# lpc11c14.net
KiCad netlist of a schematic drawn in Altium Designer
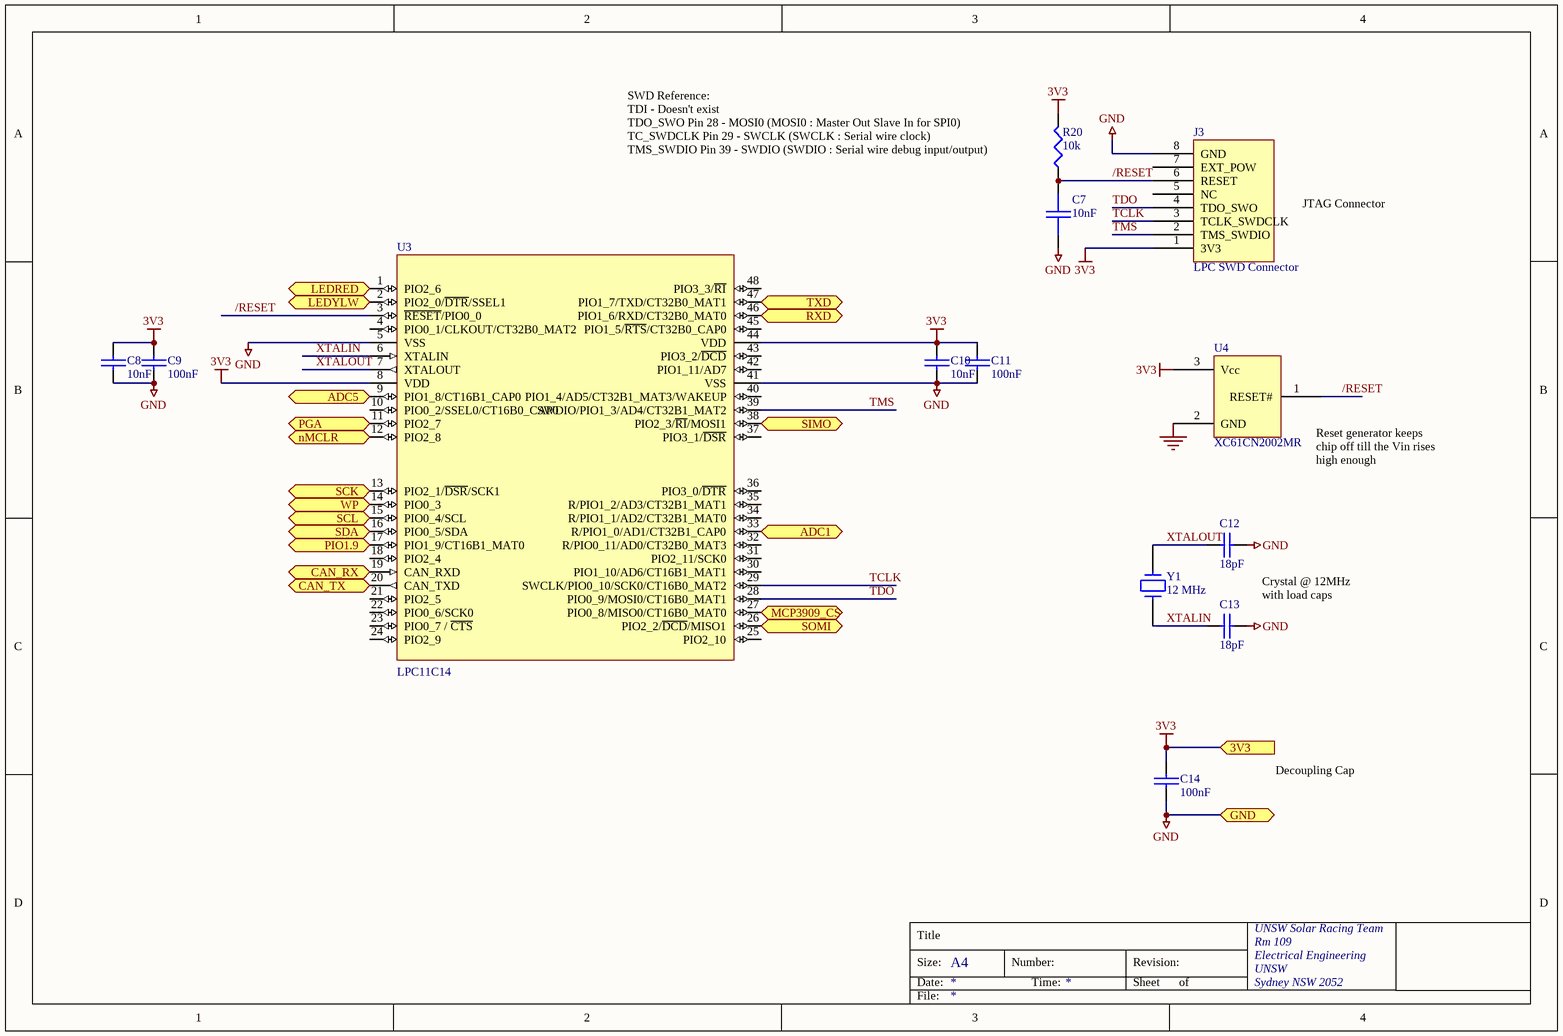
[diagram p0: lpc11c14.SchDoc]

(export (version "E")
  (design (tool "Eeschema 10.0.6"))
  (components
    (comp (ref "C7")
      (value "10nF")
      (footprint "0603")
      (description "Capacitor")
      (libsource (lib "SunswiftLib20030312RR") (part "CAP"))
    )
    (comp (ref "C8")
      (value "10nF")
      (footprint "0603")
      (description "Capacitor")
      (libsource (lib "*") (part "CAP"))
    )
    (comp (ref "C9")
      (value "100nF")
      (footprint "0603")
      (description "Capacitor")
      (libsource (lib "*") (part "CAP"))
    )
    (comp (ref "C10")
      (value "10nF")
      (footprint "0603")
      (description "Capacitor")
      (libsource (lib "*") (part "CAP"))
    )
    (comp (ref "C11")
      (value "100nF")
      (footprint "0603")
      (description "Capacitor")
      (libsource (lib "*") (part "CAP"))
    )
    (comp (ref "C12")
      (value "18pF")
      (footprint "0603")
      (description "Capacitor")
      (libsource (lib "*") (part "CAP"))
    )
    (comp (ref "C13")
      (value "18pF")
      (footprint "0603")
      (description "Capacitor")
      (libsource (lib "*") (part "CAP"))
    )
    (comp (ref "C14")
      (value "100nF")
      (footprint "0603")
      (description "Capacitor")
      (libsource (lib "*") (part "CAP"))
    )
    (comp (ref "J3")
      (value "LPC SWD Connector")
      (footprint "IDC8")
      (libsource (lib "2009_BatteryMaster") (part "LPCLink_Connector"))
    )
    (comp (ref "R20")
      (value "10k")
      (footprint "0603")
      (description "Resistor")
      (libsource (lib "SunswiftLib20030312RR") (part "RES1"))
    )
    (comp (ref "U3")
      (value "LPC11C14")
      (footprint "Quad48-LPC11c14")
      (libsource (lib "LPC") (part "LPC11C14_Full"))
    )
    (comp (ref "U4")
      (value "XC61CN2002MR")
      (footprint "SOT23-3")
      (description "SOT23 reset generator")
      (libsource (lib "*") (part "XC61F"))
    )
    (comp (ref "Y1")
      (value "12 MHz")
      (footprint "HC49/4H")
      (description "Crystal")
      (libsource (lib "*") (part "CRYSTAL"))
    )
  )
  (nets
    (net (code "1") (name "/ADC1") (class "Default")
      (node (ref "U3") (pin "33") (pinfunction "R/PIO1_0/AD1/CT32B1_CAP0_33") (pintype "bidirectional"))
    )
    (net (code "2") (name "/ADC5") (class "Default")
      (node (ref "U3") (pin "9") (pinfunction "PIO1_8/CT16B1_CAP0_9") (pintype "bidirectional"))
    )
    (net (code "3") (name "/CAN_RX") (class "Default")
      (node (ref "U3") (pin "19") (pinfunction "CAN_RXD_19") (pintype "input"))
    )
    (net (code "4") (name "/CAN_TX") (class "Default")
      (node (ref "U3") (pin "20") (pinfunction "CAN_TXD_20") (pintype "output"))
    )
    (net (code "5") (name "/LEDRED") (class "Default")
      (node (ref "U3") (pin "1") (pinfunction "PIO2_6_1") (pintype "bidirectional"))
    )
    (net (code "6") (name "/LEDYLW") (class "Default")
      (node (ref "U3") (pin "2") (pinfunction "PIO2_0/~{DTR}/SSEL1_2") (pintype "bidirectional"))
    )
    (net (code "7") (name "/MCP3909_CS") (class "Default")
      (node (ref "U3") (pin "27") (pinfunction "PIO0_8/MISO0/CT16B0_MAT0_27") (pintype "bidirectional"))
    )
    (net (code "8") (name "/PGA") (class "Default")
      (node (ref "U3") (pin "11") (pinfunction "PIO2_7_11") (pintype "bidirectional"))
    )
    (net (code "9") (name "/PIO1.9") (class "Default")
      (node (ref "U3") (pin "17") (pinfunction "PIO1_9/CT16B1_MAT0_17") (pintype "bidirectional"))
    )
    (net (code "10") (name "/RXD") (class "Default")
      (node (ref "U3") (pin "46") (pinfunction "PIO1_6/RXD/CT32B0_MAT0_46") (pintype "bidirectional"))
    )
    (net (code "11") (name "/SCK") (class "Default")
      (node (ref "U3") (pin "13") (pinfunction "PIO2_1/~{DSR}/SCK1_13") (pintype "bidirectional"))
    )
    (net (code "12") (name "/SCL") (class "Default")
      (node (ref "U3") (pin "15") (pinfunction "PIO0_4/SCL_15") (pintype "bidirectional"))
    )
    (net (code "13") (name "/SDA") (class "Default")
      (node (ref "U3") (pin "16") (pinfunction "PIO0_5/SDA_16") (pintype "bidirectional"))
    )
    (net (code "14") (name "/SIMO") (class "Default")
      (node (ref "U3") (pin "38") (pinfunction "PIO2_3/~{RI}/MOSI1_38") (pintype "bidirectional"))
    )
    (net (code "15") (name "/SOMI") (class "Default")
      (node (ref "U3") (pin "26") (pinfunction "PIO2_2/~{DCD}/MISO1_26") (pintype "bidirectional"))
    )
    (net (code "16") (name "/TCLK") (class "Default")
      (node (ref "J3") (pin "3") (pinfunction "TCLK_SWDCLK_3") (pintype "passive"))
      (node (ref "U3") (pin "29") (pinfunction "SWCLK/PIO0_10/SCK0/CT16B0_MAT2_29") (pintype "bidirectional"))
    )
    (net (code "17") (name "/TDO") (class "Default")
      (node (ref "J3") (pin "4") (pinfunction "TDO_SWO_4") (pintype "passive"))
      (node (ref "U3") (pin "28") (pinfunction "PIO0_9/MOSI0/CT16B0_MAT1_28") (pintype "bidirectional"))
    )
    (net (code "18") (name "/TMS") (class "Default")
      (node (ref "J3") (pin "2") (pinfunction "TMS_SWDIO_2") (pintype "passive"))
      (node (ref "U3") (pin "39") (pinfunction "SWDIO/PIO1_3/AD4/CT32B1_MAT2_39") (pintype "bidirectional"))
    )
    (net (code "19") (name "/TXD") (class "Default")
      (node (ref "U3") (pin "47") (pinfunction "PIO1_7/TXD/CT32B0_MAT1_47") (pintype "bidirectional"))
    )
    (net (code "20") (name "/WP") (class "Default")
      (node (ref "U3") (pin "14") (pinfunction "PIO0_3_14") (pintype "bidirectional"))
    )
    (net (code "21") (name "/XTALIN") (class "Default")
      (node (ref "C13") (pin "1") (pinfunction "1_1") (pintype "passive"))
      (node (ref "U3") (pin "6") (pinfunction "XTALIN_6") (pintype "input"))
      (node (ref "Y1") (pin "1") (pinfunction "1_1") (pintype "passive"))
    )
    (net (code "22") (name "/XTALOUT") (class "Default")
      (node (ref "C12") (pin "1") (pinfunction "1_1") (pintype "passive"))
      (node (ref "U3") (pin "7") (pinfunction "XTALOUT_7") (pintype "output"))
      (node (ref "Y1") (pin "2") (pinfunction "2_2") (pintype "passive"))
    )
    (net (code "23") (name "/nMCLR") (class "Default")
      (node (ref "U3") (pin "12") (pinfunction "PIO2_8_12") (pintype "bidirectional"))
    )
    (net (code "24") (name "/{slash}RESET") (class "Default")
      (node (ref "C7") (pin "1") (pinfunction "1_1") (pintype "passive"))
      (node (ref "J3") (pin "6") (pinfunction "RESET_6") (pintype "passive"))
      (node (ref "R20") (pin "1") (pinfunction "1_1") (pintype "passive"))
      (node (ref "U3") (pin "3") (pinfunction "~{RESET}/PIO0_0_3") (pintype "bidirectional"))
      (node (ref "U4") (pin "1") (pinfunction "RESET#_1") (pintype "passive"))
    )
    (net (code "25") (name "3V3") (class "Default")
      (node (ref "C10") (pin "2") (pinfunction "2_2") (pintype "passive"))
      (node (ref "C11") (pin "2") (pinfunction "2_2") (pintype "passive"))
      (node (ref "C14") (pin "1") (pinfunction "1_1") (pintype "passive"))
      (node (ref "C8") (pin "2") (pinfunction "2_2") (pintype "passive"))
      (node (ref "C9") (pin "2") (pinfunction "2_2") (pintype "passive"))
      (node (ref "J3") (pin "1") (pinfunction "3V3_1") (pintype "passive"))
      (node (ref "R20") (pin "2") (pinfunction "2_2") (pintype "passive"))
      (node (ref "U3") (pin "44") (pinfunction "VDD_44") (pintype "power_in"))
      (node (ref "U3") (pin "8") (pinfunction "VDD_8") (pintype "power_in"))
      (node (ref "U4") (pin "3") (pinfunction "Vcc_3") (pintype "passive"))
    )
    (net (code "26") (name "GND") (class "Default")
      (node (ref "C10") (pin "1") (pinfunction "1_1") (pintype "passive"))
      (node (ref "C11") (pin "1") (pinfunction "1_1") (pintype "passive"))
      (node (ref "C12") (pin "2") (pinfunction "2_2") (pintype "passive"))
      (node (ref "C13") (pin "2") (pinfunction "2_2") (pintype "passive"))
      (node (ref "C14") (pin "2") (pinfunction "2_2") (pintype "passive"))
      (node (ref "C7") (pin "2") (pinfunction "2_2") (pintype "passive"))
      (node (ref "C8") (pin "1") (pinfunction "1_1") (pintype "passive"))
      (node (ref "C9") (pin "1") (pinfunction "1_1") (pintype "passive"))
      (node (ref "J3") (pin "8") (pinfunction "GND_8") (pintype "passive"))
      (node (ref "U3") (pin "41") (pinfunction "VSS_41") (pintype "power_in"))
      (node (ref "U3") (pin "5") (pinfunction "VSS_5") (pintype "power_in"))
      (node (ref "U4") (pin "2") (pinfunction "GND_2") (pintype "passive"))
    )
    (net (code "27") (name "unconnected-(J3-EXT_POW-Pad7)") (class "Default")
      (node (ref "J3") (pin "7") (pinfunction "EXT_POW_7") (pintype "passive"))
    )
    (net (code "28") (name "unconnected-(J3-NC-Pad5)") (class "Default")
      (node (ref "J3") (pin "5") (pinfunction "NC_5") (pintype "passive"))
    )
    (net (code "29") (name "unconnected-(U3-PIO0_1{slash}CLKOUT{slash}CT32B0_MAT2-Pad4)") (class "Default")
      (node (ref "U3") (pin "4") (pinfunction "PIO0_1/CLKOUT/CT32B0_MAT2_4") (pintype "bidirectional"))
    )
    (net (code "30") (name "unconnected-(U3-PIO0_2{slash}SSEL0{slash}CT16B0_CAP0-Pad10)") (class "Default")
      (node (ref "U3") (pin "10") (pinfunction "PIO0_2/SSEL0/CT16B0_CAP0_10") (pintype "bidirectional"))
    )
    (net (code "31") (name "unconnected-(U3-PIO0_6{slash}SCK0-Pad22)") (class "Default")
      (node (ref "U3") (pin "22") (pinfunction "PIO0_6/SCK0_22") (pintype "bidirectional"))
    )
    (net (code "32") (name "unconnected-(U3-PIO0_7_{slash}_~{CTS}-Pad23)") (class "Default")
      (node (ref "U3") (pin "23") (pinfunction "PIO0_7_/_~{CTS}_23") (pintype "bidirectional"))
    )
    (net (code "33") (name "unconnected-(U3-PIO1_4{slash}AD5{slash}CT32B1_MAT3{slash}WAKEUP-Pad40)") (class "Default")
      (node (ref "U3") (pin "40") (pinfunction "PIO1_4/AD5/CT32B1_MAT3/WAKEUP_40") (pintype "bidirectional"))
    )
    (net (code "34") (name "unconnected-(U3-PIO1_5{slash}~{RTS}{slash}CT32B0_CAP0-Pad45)") (class "Default")
      (node (ref "U3") (pin "45") (pinfunction "PIO1_5/~{RTS}/CT32B0_CAP0_45") (pintype "bidirectional"))
    )
    (net (code "35") (name "unconnected-(U3-PIO1_10{slash}AD6{slash}CT16B1_MAT1-Pad30)") (class "Default")
      (node (ref "U3") (pin "30") (pinfunction "PIO1_10/AD6/CT16B1_MAT1_30") (pintype "bidirectional"))
    )
    (net (code "36") (name "unconnected-(U3-PIO1_11{slash}AD7-Pad42)") (class "Default")
      (node (ref "U3") (pin "42") (pinfunction "PIO1_11/AD7_42") (pintype "bidirectional"))
    )
    (net (code "37") (name "unconnected-(U3-PIO2_4-Pad18)") (class "Default")
      (node (ref "U3") (pin "18") (pinfunction "PIO2_4_18") (pintype "bidirectional"))
    )
    (net (code "38") (name "unconnected-(U3-PIO2_5-Pad21)") (class "Default")
      (node (ref "U3") (pin "21") (pinfunction "PIO2_5_21") (pintype "bidirectional"))
    )
    (net (code "39") (name "unconnected-(U3-PIO2_9-Pad24)") (class "Default")
      (node (ref "U3") (pin "24") (pinfunction "PIO2_9_24") (pintype "bidirectional"))
    )
    (net (code "40") (name "unconnected-(U3-PIO2_10-Pad25)") (class "Default")
      (node (ref "U3") (pin "25") (pinfunction "PIO2_10_25") (pintype "bidirectional"))
    )
    (net (code "41") (name "unconnected-(U3-PIO2_11{slash}SCK0-Pad31)") (class "Default")
      (node (ref "U3") (pin "31") (pinfunction "PIO2_11/SCK0_31") (pintype "bidirectional"))
    )
    (net (code "42") (name "unconnected-(U3-PIO3_0{slash}~{DTR}-Pad36)") (class "Default")
      (node (ref "U3") (pin "36") (pinfunction "PIO3_0/~{DTR}_36") (pintype "bidirectional"))
    )
    (net (code "43") (name "unconnected-(U3-PIO3_1{slash}~{DSR}-Pad37)") (class "Default")
      (node (ref "U3") (pin "37") (pinfunction "PIO3_1/~{DSR}_37") (pintype "bidirectional"))
    )
    (net (code "44") (name "unconnected-(U3-PIO3_2{slash}~{DCD}-Pad43)") (class "Default")
      (node (ref "U3") (pin "43") (pinfunction "PIO3_2/~{DCD}_43") (pintype "bidirectional"))
    )
    (net (code "45") (name "unconnected-(U3-PIO3_3{slash}~{RI}-Pad48)") (class "Default")
      (node (ref "U3") (pin "48") (pinfunction "PIO3_3/~{RI}_48") (pintype "bidirectional"))
    )
    (net (code "46") (name "unconnected-(U3-R{slash}PIO0_11{slash}AD0{slash}CT32B0_MAT3-Pad32)") (class "Default")
      (node (ref "U3") (pin "32") (pinfunction "R/PIO0_11/AD0/CT32B0_MAT3_32") (pintype "bidirectional"))
    )
    (net (code "47") (name "unconnected-(U3-R{slash}PIO1_1{slash}AD2{slash}CT32B1_MAT0-Pad34)") (class "Default")
      (node (ref "U3") (pin "34") (pinfunction "R/PIO1_1/AD2/CT32B1_MAT0_34") (pintype "bidirectional"))
    )
    (net (code "48") (name "unconnected-(U3-R{slash}PIO1_2{slash}AD3{slash}CT32B1_MAT1-Pad35)") (class "Default")
      (node (ref "U3") (pin "35") (pinfunction "R/PIO1_2/AD3/CT32B1_MAT1_35") (pintype "bidirectional"))
    )
  )
)
